# DiffMeasure.net
KiCad netlist of a schematic drawn in Altium Designer
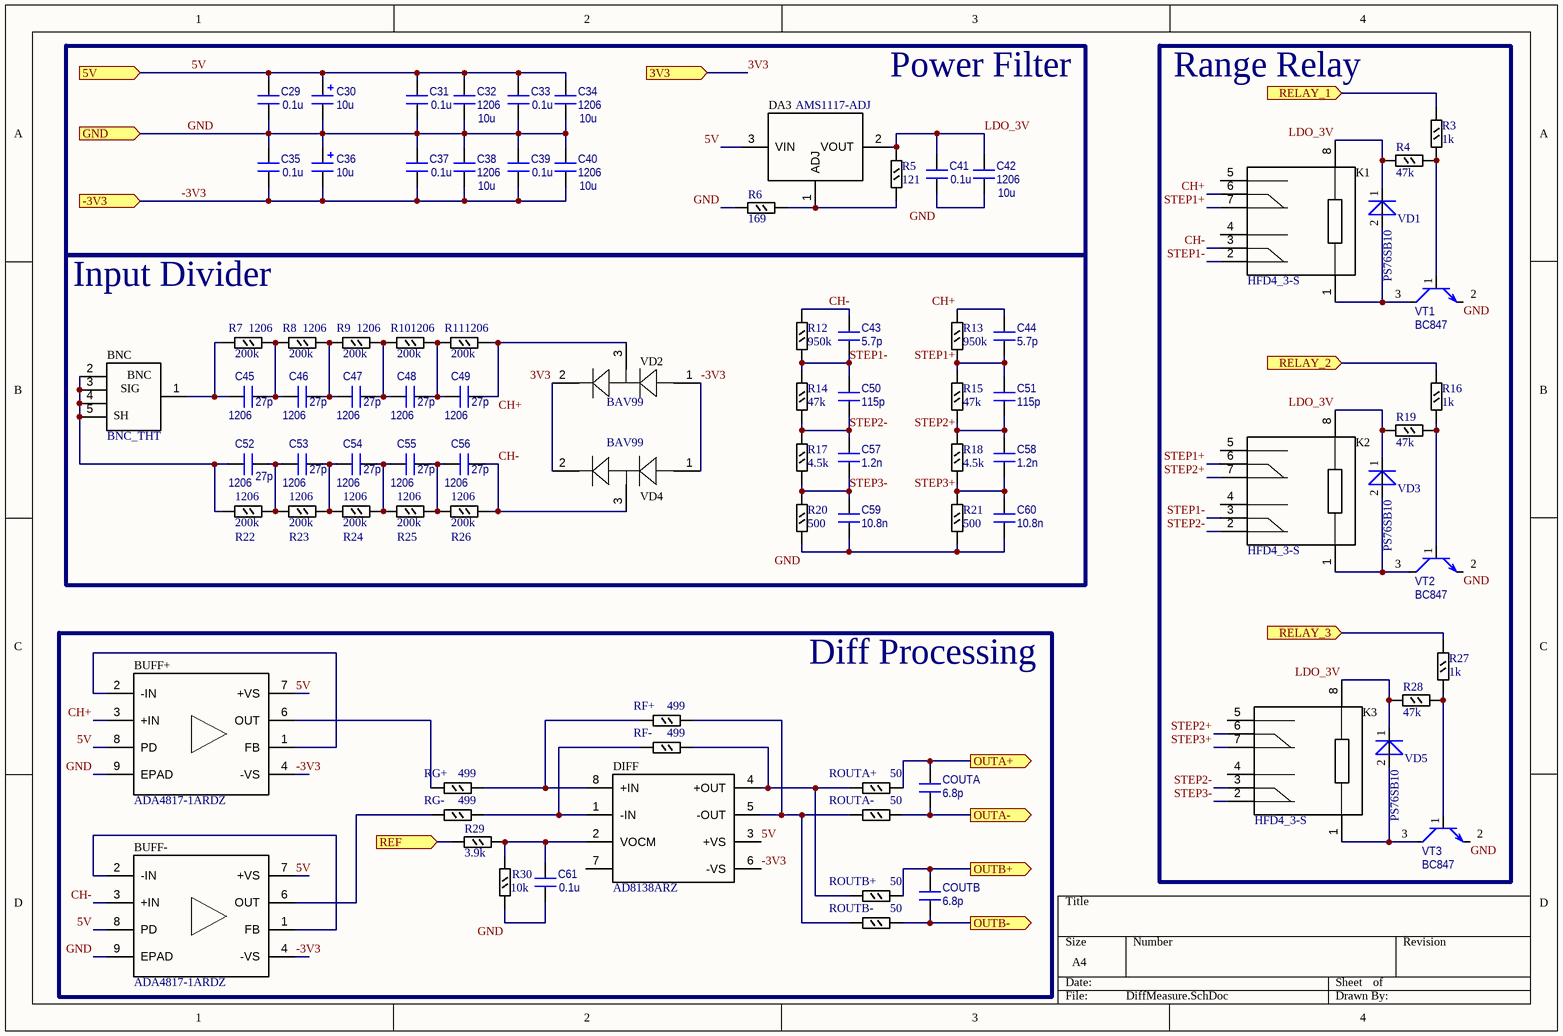
[diagram p0: DiffMeasure.SchDoc]

(export (version "E")
  (design (tool "Eeschema 10.0.6"))
  (components
    (comp (ref "BNC")
      (value "BNC_THT")
      (footprint "BNC_VERTICAL_THT_5PIN")
      (description "Generic vertical BNC jack, five through-hole terminals")
      (libsource (lib "Oscill") (part "BNC_VERTICAL_THT"))
    )
    (comp (ref "BUFF+")
      (value "ADA4817-1ARDZ")
      (footprint "ADA4817-1ARDZ_SOIC8_EP")
      (description "ADI ADA4817-1ARDZ FastFET op amp, RD-8-4 SOIC-8 with EP")
      (libsource (lib "Oscill") (part "ADA4817-1ARDZ"))
    )
    (comp (ref "BUFF-")
      (value "ADA4817-1ARDZ")
      (footprint "ADA4817-1ARDZ_SOIC8_EP")
      (description "ADI ADA4817-1ARDZ FastFET op amp, RD-8-4 SOIC-8 with EP")
      (libsource (lib "Oscill") (part "ADA4817-1ARDZ"))
    )
    (comp (ref "C29")
      (value "0.1u")
      (footprint "CAPC2012(0805)N")
      (fields (field (name "PART NUMBER") "CAPC2012(0805)"))
      (libsource (lib "SssAccesDatbase") (part "Capacitor generic"))
    )
    (comp (ref "C30")
      (value "10u")
      (footprint "CAPMP7343X310N")
      (fields (field (name "PART NUMBER") "CapTantD"))
      (libsource (lib "SssAccesDatbase") (part "Capacitor generic polar"))
    )
    (comp (ref "C31")
      (value "0.1u")
      (footprint "CAPC2012(0805)N")
      (fields (field (name "PART NUMBER") "CAPC2012(0805)"))
      (libsource (lib "SssAccesDatbase") (part "Capacitor generic"))
    )
    (comp (ref "C32")
      (value "10u")
      (footprint "CAP_CER_1206")
      (description "Cap Cer MLCC SMD 50V 2700p C0G NP0 1206 2%")
      (fields
        (field (name "PACKAGE") "1206")
        (field (name "PART NUMBER") "12065A272GAT2A")
        (field (name "MOUSER PART NUMBER") "581-12065A272G")
      )
      (libsource (lib "SssAccesDatbase") (part "Capacitor generic"))
    )
    (comp (ref "C33")
      (value "0.1u")
      (footprint "CAPC2012(0805)N")
      (fields (field (name "PART NUMBER") "CAPC2012(0805)"))
      (libsource (lib "SssAccesDatbase") (part "Capacitor generic"))
    )
    (comp (ref "C34")
      (value "10u")
      (footprint "CAP_CER_1206")
      (description "Cap Cer MLCC SMD 50V 2700p C0G NP0 1206 2%")
      (fields
        (field (name "PACKAGE") "1206")
        (field (name "PART NUMBER") "12065A272GAT2A")
        (field (name "MOUSER PART NUMBER") "581-12065A272G")
      )
      (libsource (lib "SssAccesDatbase") (part "Capacitor generic"))
    )
    (comp (ref "C35")
      (value "0.1u")
      (footprint "CAPC2012(0805)N")
      (fields (field (name "PART NUMBER") "CAPC2012(0805)"))
      (libsource (lib "SssAccesDatbase") (part "Capacitor generic"))
    )
    (comp (ref "C36")
      (value "10u")
      (footprint "CAPMP7343X310N")
      (fields (field (name "PART NUMBER") "CapTantD"))
      (libsource (lib "SssAccesDatbase") (part "Capacitor generic polar"))
    )
    (comp (ref "C37")
      (value "0.1u")
      (footprint "CAPC2012(0805)N")
      (fields (field (name "PART NUMBER") "CAPC2012(0805)"))
      (libsource (lib "SssAccesDatbase") (part "Capacitor generic"))
    )
    (comp (ref "C38")
      (value "10u")
      (footprint "CAP_CER_1206")
      (description "Cap Cer MLCC SMD 50V 2700p C0G NP0 1206 2%")
      (fields
        (field (name "PACKAGE") "1206")
        (field (name "PART NUMBER") "12065A272GAT2A")
        (field (name "MOUSER PART NUMBER") "581-12065A272G")
      )
      (libsource (lib "SssAccesDatbase") (part "Capacitor generic"))
    )
    (comp (ref "C39")
      (value "0.1u")
      (footprint "CAPC2012(0805)N")
      (fields (field (name "PART NUMBER") "CAPC2012(0805)"))
      (libsource (lib "SssAccesDatbase") (part "Capacitor generic"))
    )
    (comp (ref "C40")
      (value "10u")
      (footprint "CAP_CER_1206")
      (description "Cap Cer MLCC SMD 50V 2700p C0G NP0 1206 2%")
      (fields
        (field (name "PACKAGE") "1206")
        (field (name "PART NUMBER") "12065A272GAT2A")
        (field (name "MOUSER PART NUMBER") "581-12065A272G")
      )
      (libsource (lib "SssAccesDatbase") (part "Capacitor generic"))
    )
    (comp (ref "C41")
      (value "0.1u")
      (footprint "CAPC2012(0805)N")
      (fields (field (name "PART NUMBER") "CAPC2012(0805)"))
      (libsource (lib "SssAccesDatbase") (part "Capacitor generic"))
    )
    (comp (ref "C42")
      (value "10u")
      (footprint "CAP_CER_1206")
      (description "Cap Cer MLCC SMD 50V 2700p C0G NP0 1206 2%")
      (fields
        (field (name "PACKAGE") "1206")
        (field (name "PART NUMBER") "12065A272GAT2A")
        (field (name "MOUSER PART NUMBER") "581-12065A272G")
      )
      (libsource (lib "SssAccesDatbase") (part "Capacitor generic"))
    )
    (comp (ref "C43")
      (value "5.7p")
      (footprint "CAPC2012(0805)N")
      (fields (field (name "PART NUMBER") "CAPC2012(0805)"))
      (libsource (lib "SssAccesDatbase") (part "Capacitor generic"))
    )
    (comp (ref "C44")
      (value "5.7p")
      (footprint "CAPC2012(0805)N")
      (fields (field (name "PART NUMBER") "CAPC2012(0805)"))
      (libsource (lib "SssAccesDatbase") (part "Capacitor generic"))
    )
    (comp (ref "C45")
      (value "27p")
      (footprint "CAP_CER_1206")
      (description "Cap Cer MLCC SMD 50V 2700p C0G NP0 1206 2%")
      (fields
        (field (name "PACKAGE") "1206")
        (field (name "PART NUMBER") "12065A272GAT2A")
        (field (name "MOUSER PART NUMBER") "581-12065A272G")
      )
      (libsource (lib "SssAccesDatbase") (part "Capacitor generic"))
    )
    (comp (ref "C46")
      (value "27p")
      (footprint "CAP_CER_1206")
      (description "Cap Cer MLCC SMD 50V 2700p C0G NP0 1206 2%")
      (fields
        (field (name "PACKAGE") "1206")
        (field (name "PART NUMBER") "12065A272GAT2A")
        (field (name "MOUSER PART NUMBER") "581-12065A272G")
      )
      (libsource (lib "SssAccesDatbase") (part "Capacitor generic"))
    )
    (comp (ref "C47")
      (value "27p")
      (footprint "CAP_CER_1206")
      (description "Cap Cer MLCC SMD 50V 2700p C0G NP0 1206 2%")
      (fields
        (field (name "PACKAGE") "1206")
        (field (name "PART NUMBER") "12065A272GAT2A")
        (field (name "MOUSER PART NUMBER") "581-12065A272G")
      )
      (libsource (lib "SssAccesDatbase") (part "Capacitor generic"))
    )
    (comp (ref "C48")
      (value "27p")
      (footprint "CAP_CER_1206")
      (description "Cap Cer MLCC SMD 50V 2700p C0G NP0 1206 2%")
      (fields
        (field (name "PACKAGE") "1206")
        (field (name "PART NUMBER") "12065A272GAT2A")
        (field (name "MOUSER PART NUMBER") "581-12065A272G")
      )
      (libsource (lib "SssAccesDatbase") (part "Capacitor generic"))
    )
    (comp (ref "C49")
      (value "27p")
      (footprint "CAP_CER_1206")
      (description "Cap Cer MLCC SMD 50V 2700p C0G NP0 1206 2%")
      (fields
        (field (name "PACKAGE") "1206")
        (field (name "PART NUMBER") "12065A272GAT2A")
        (field (name "MOUSER PART NUMBER") "581-12065A272G")
      )
      (libsource (lib "SssAccesDatbase") (part "Capacitor generic"))
    )
    (comp (ref "C50")
      (value "115p")
      (footprint "CAPC2012(0805)N")
      (fields (field (name "PART NUMBER") "CAPC2012(0805)"))
      (libsource (lib "SssAccesDatbase") (part "Capacitor generic"))
    )
    (comp (ref "C51")
      (value "115p")
      (footprint "CAPC2012(0805)N")
      (fields (field (name "PART NUMBER") "CAPC2012(0805)"))
      (libsource (lib "SssAccesDatbase") (part "Capacitor generic"))
    )
    (comp (ref "C52")
      (value "27p")
      (footprint "CAP_CER_1206")
      (description "Cap Cer MLCC SMD 50V 2700p C0G NP0 1206 2%")
      (fields
        (field (name "PACKAGE") "1206")
        (field (name "PART NUMBER") "12065A272GAT2A")
        (field (name "MOUSER PART NUMBER") "581-12065A272G")
      )
      (libsource (lib "SssAccesDatbase") (part "Capacitor generic"))
    )
    (comp (ref "C53")
      (value "27p")
      (footprint "CAP_CER_1206")
      (description "Cap Cer MLCC SMD 50V 2700p C0G NP0 1206 2%")
      (fields
        (field (name "PACKAGE") "1206")
        (field (name "PART NUMBER") "12065A272GAT2A")
        (field (name "MOUSER PART NUMBER") "581-12065A272G")
      )
      (libsource (lib "SssAccesDatbase") (part "Capacitor generic"))
    )
    (comp (ref "C54")
      (value "27p")
      (footprint "CAP_CER_1206")
      (description "Cap Cer MLCC SMD 50V 2700p C0G NP0 1206 2%")
      (fields
        (field (name "PACKAGE") "1206")
        (field (name "PART NUMBER") "12065A272GAT2A")
        (field (name "MOUSER PART NUMBER") "581-12065A272G")
      )
      (libsource (lib "SssAccesDatbase") (part "Capacitor generic"))
    )
    (comp (ref "C55")
      (value "27p")
      (footprint "CAP_CER_1206")
      (description "Cap Cer MLCC SMD 50V 2700p C0G NP0 1206 2%")
      (fields
        (field (name "PACKAGE") "1206")
        (field (name "PART NUMBER") "12065A272GAT2A")
        (field (name "MOUSER PART NUMBER") "581-12065A272G")
      )
      (libsource (lib "SssAccesDatbase") (part "Capacitor generic"))
    )
    (comp (ref "C56")
      (value "27p")
      (footprint "CAP_CER_1206")
      (description "Cap Cer MLCC SMD 50V 2700p C0G NP0 1206 2%")
      (fields
        (field (name "PACKAGE") "1206")
        (field (name "PART NUMBER") "12065A272GAT2A")
        (field (name "MOUSER PART NUMBER") "581-12065A272G")
      )
      (libsource (lib "SssAccesDatbase") (part "Capacitor generic"))
    )
    (comp (ref "C57")
      (value "1.2n")
      (footprint "CAPC2012(0805)N")
      (fields (field (name "PART NUMBER") "CAPC2012(0805)"))
      (libsource (lib "SssAccesDatbase") (part "Capacitor generic"))
    )
    (comp (ref "C58")
      (value "1.2n")
      (footprint "CAPC2012(0805)N")
      (fields (field (name "PART NUMBER") "CAPC2012(0805)"))
      (libsource (lib "SssAccesDatbase") (part "Capacitor generic"))
    )
    (comp (ref "C59")
      (value "10.8n")
      (footprint "CAPC2012(0805)N")
      (fields (field (name "PART NUMBER") "CAPC2012(0805)"))
      (libsource (lib "SssAccesDatbase") (part "Capacitor generic"))
    )
    (comp (ref "C60")
      (value "10.8n")
      (footprint "CAPC2012(0805)N")
      (fields (field (name "PART NUMBER") "CAPC2012(0805)"))
      (libsource (lib "SssAccesDatbase") (part "Capacitor generic"))
    )
    (comp (ref "C61")
      (value "0.1u")
      (footprint "CAPC2012(0805)N")
      (fields (field (name "PART NUMBER") "CAPC2012(0805)"))
      (libsource (lib "SssAccesDatbase") (part "Capacitor generic"))
    )
    (comp (ref "COUTA")
      (value "6.8p")
      (footprint "CAPC2012(0805)N")
      (fields (field (name "PART NUMBER") "CAPC2012(0805)"))
      (libsource (lib "SssAccesDatbase") (part "Capacitor generic"))
    )
    (comp (ref "COUTB")
      (value "6.8p")
      (footprint "CAPC2012(0805)N")
      (fields (field (name "PART NUMBER") "CAPC2012(0805)"))
      (libsource (lib "SssAccesDatbase") (part "Capacitor generic"))
    )
    (comp (ref "DA3")
      (value "AMS1117-ADJ")
      (footprint "Oscill:AMS1117-ADJ_SOT223")
      (description "AMS1117 adjustable voltage regulator, SOT-223; tab = VOUT")
      (libsource (lib "Oscill") (part "AMS1117-ADJ"))
    )
    (comp (ref "DIFF")
      (value "AD8138ARZ")
      (footprint "AD8138ARZ_SOIC8")
      (description "ADI AD8138ARZ low distortion differential ADC driver, SOIC-8 R-8")
      (libsource (lib "Oscill") (part "AD8138ARZ"))
    )
    (comp (ref "K1")
      (value "HFD4_3-S")
      (footprint "Oscill:HFD4_3_S_SMT")
      (description "Hongfa HFD4/3-S monostable DPDT relay, standard SMT terminal")
      (libsource (lib "Oscill") (part "HFD4_3-S"))
    )
    (comp (ref "K2")
      (value "HFD4_3-S")
      (footprint "Oscill:HFD4_3_S_SMT")
      (description "Hongfa HFD4/3-S monostable DPDT relay, standard SMT terminal")
      (libsource (lib "Oscill") (part "HFD4_3-S"))
    )
    (comp (ref "K3")
      (value "HFD4_3-S")
      (footprint "Oscill:HFD4_3_S_SMT")
      (description "Hongfa HFD4/3-S monostable DPDT relay, standard SMT terminal")
      (libsource (lib "Oscill") (part "HFD4_3-S"))
    )
    (comp (ref "R3")
      (value "1k")
      (footprint "RESC2012(0805)N")
      (fields (field (name "PART NUMBER") "RESC2012(0805)"))
      (libsource (lib "") (part "Resistor 0,125W_1"))
    )
    (comp (ref "R4")
      (value "47k")
      (footprint "RESC2012(0805)N")
      (fields (field (name "PART NUMBER") "RESC2012(0805)"))
      (libsource (lib "") (part "Resistor 0,125W_3"))
    )
    (comp (ref "R5")
      (value "121")
      (footprint "RESC2012(0805)N")
      (fields (field (name "PART NUMBER") "RESC2012(0805)"))
      (libsource (lib "") (part "Resistor 0,125W_1"))
    )
    (comp (ref "R6")
      (value "169")
      (footprint "RESC2012(0805)N")
      (fields (field (name "PART NUMBER") "RESC2012(0805)"))
      (libsource (lib "SssAccesDatbase") (part "Resistor 0,125W"))
    )
    (comp (ref "R7")
      (value "200k")
      (footprint "Oscill:R_1206")
      (fields (field (name "PART NUMBER") "RESC2012(0805)") (field (name "PACKAGE") "1206"))
      (libsource (lib "SssAccesDatbase") (part "Resistor 0,125W"))
    )
    (comp (ref "R8")
      (value "200k")
      (footprint "Oscill:R_1206")
      (fields (field (name "PART NUMBER") "RESC2012(0805)") (field (name "PACKAGE") "1206"))
      (libsource (lib "SssAccesDatbase") (part "Resistor 0,125W"))
    )
    (comp (ref "R9")
      (value "200k")
      (footprint "Oscill:R_1206")
      (fields (field (name "PART NUMBER") "RESC2012(0805)") (field (name "PACKAGE") "1206"))
      (libsource (lib "SssAccesDatbase") (part "Resistor 0,125W"))
    )
    (comp (ref "R10")
      (value "200k")
      (footprint "Oscill:R_1206")
      (fields (field (name "PART NUMBER") "RESC2012(0805)") (field (name "PACKAGE") "1206"))
      (libsource (lib "SssAccesDatbase") (part "Resistor 0,125W"))
    )
    (comp (ref "R11")
      (value "200k")
      (footprint "Oscill:R_1206")
      (fields (field (name "PART NUMBER") "RESC2012(0805)") (field (name "PACKAGE") "1206"))
      (libsource (lib "SssAccesDatbase") (part "Resistor 0,125W"))
    )
    (comp (ref "R12")
      (value "950k")
      (footprint "RESC2012(0805)N")
      (fields (field (name "PART NUMBER") "RESC2012(0805)"))
      (libsource (lib "") (part "Resistor 0,125W_2"))
    )
    (comp (ref "R13")
      (value "950k")
      (footprint "RESC2012(0805)N")
      (fields (field (name "PART NUMBER") "RESC2012(0805)"))
      (libsource (lib "") (part "Resistor 0,125W_2"))
    )
    (comp (ref "R14")
      (value "47k")
      (footprint "RESC2012(0805)N")
      (fields (field (name "PART NUMBER") "RESC2012(0805)"))
      (libsource (lib "") (part "Resistor 0,125W_2"))
    )
    (comp (ref "R15")
      (value "47k")
      (footprint "RESC2012(0805)N")
      (fields (field (name "PART NUMBER") "RESC2012(0805)"))
      (libsource (lib "") (part "Resistor 0,125W_2"))
    )
    (comp (ref "R16")
      (value "1k")
      (footprint "RESC2012(0805)N")
      (fields (field (name "PART NUMBER") "RESC2012(0805)"))
      (libsource (lib "") (part "Resistor 0,125W_1"))
    )
    (comp (ref "R17")
      (value "4.5k")
      (footprint "RESC2012(0805)N")
      (fields (field (name "PART NUMBER") "RESC2012(0805)"))
      (libsource (lib "") (part "Resistor 0,125W_2"))
    )
    (comp (ref "R18")
      (value "4.5k")
      (footprint "RESC2012(0805)N")
      (fields (field (name "PART NUMBER") "RESC2012(0805)"))
      (libsource (lib "") (part "Resistor 0,125W_2"))
    )
    (comp (ref "R19")
      (value "47k")
      (footprint "RESC2012(0805)N")
      (fields (field (name "PART NUMBER") "RESC2012(0805)"))
      (libsource (lib "") (part "Resistor 0,125W_3"))
    )
    (comp (ref "R20")
      (value "500")
      (footprint "RESC2012(0805)N")
      (fields (field (name "PART NUMBER") "RESC2012(0805)"))
      (libsource (lib "") (part "Resistor 0,125W_2"))
    )
    (comp (ref "R21")
      (value "500")
      (footprint "RESC2012(0805)N")
      (fields (field (name "PART NUMBER") "RESC2012(0805)"))
      (libsource (lib "") (part "Resistor 0,125W_2"))
    )
    (comp (ref "R22")
      (value "200k")
      (footprint "Oscill:R_1206")
      (fields (field (name "PART NUMBER") "RESC2012(0805)") (field (name "PACKAGE") "1206"))
      (libsource (lib "SssAccesDatbase") (part "Resistor 0,125W"))
    )
    (comp (ref "R23")
      (value "200k")
      (footprint "Oscill:R_1206")
      (fields (field (name "PART NUMBER") "RESC2012(0805)") (field (name "PACKAGE") "1206"))
      (libsource (lib "SssAccesDatbase") (part "Resistor 0,125W"))
    )
    (comp (ref "R24")
      (value "200k")
      (footprint "Oscill:R_1206")
      (fields (field (name "PART NUMBER") "RESC2012(0805)") (field (name "PACKAGE") "1206"))
      (libsource (lib "SssAccesDatbase") (part "Resistor 0,125W"))
    )
    (comp (ref "R25")
      (value "200k")
      (footprint "Oscill:R_1206")
      (fields (field (name "PART NUMBER") "RESC2012(0805)") (field (name "PACKAGE") "1206"))
      (libsource (lib "SssAccesDatbase") (part "Resistor 0,125W"))
    )
    (comp (ref "R26")
      (value "200k")
      (footprint "Oscill:R_1206")
      (fields (field (name "PART NUMBER") "RESC2012(0805)") (field (name "PACKAGE") "1206"))
      (libsource (lib "SssAccesDatbase") (part "Resistor 0,125W"))
    )
    (comp (ref "R27")
      (value "1k")
      (footprint "RESC2012(0805)N")
      (fields (field (name "PART NUMBER") "RESC2012(0805)"))
      (libsource (lib "") (part "Resistor 0,125W_1"))
    )
    (comp (ref "R28")
      (value "47k")
      (footprint "RESC2012(0805)N")
      (fields (field (name "PART NUMBER") "RESC2012(0805)"))
      (libsource (lib "") (part "Resistor 0,125W_3"))
    )
    (comp (ref "R29")
      (value "3.9k")
      (footprint "RESC2012(0805)N")
      (fields (field (name "PART NUMBER") "RESC2012(0805)"))
      (libsource (lib "SssAccesDatbase") (part "Resistor 0,125W"))
    )
    (comp (ref "R30")
      (value "10k")
      (footprint "RESC2012(0805)N")
      (fields (field (name "PART NUMBER") "RESC2012(0805)"))
      (libsource (lib "") (part "Resistor 0,125W_1"))
    )
    (comp (ref "RF+")
      (value "499")
      (footprint "RESC2012(0805)N")
      (fields (field (name "PART NUMBER") "RESC2012(0805)"))
      (libsource (lib "SssAccesDatbase") (part "Resistor 0,125W"))
    )
    (comp (ref "RF-")
      (value "499")
      (footprint "RESC2012(0805)N")
      (fields (field (name "PART NUMBER") "RESC2012(0805)"))
      (libsource (lib "SssAccesDatbase") (part "Resistor 0,125W"))
    )
    (comp (ref "RG+")
      (value "499")
      (footprint "RESC2012(0805)N")
      (fields (field (name "PART NUMBER") "RESC2012(0805)"))
      (libsource (lib "SssAccesDatbase") (part "Resistor 0,125W"))
    )
    (comp (ref "RG-")
      (value "499")
      (footprint "RESC2012(0805)N")
      (fields (field (name "PART NUMBER") "RESC2012(0805)"))
      (libsource (lib "SssAccesDatbase") (part "Resistor 0,125W"))
    )
    (comp (ref "ROUTA+")
      (value "50")
      (footprint "RESC2012(0805)N")
      (fields (field (name "PART NUMBER") "RESC2012(0805)"))
      (libsource (lib "SssAccesDatbase") (part "Resistor 0,125W"))
    )
    (comp (ref "ROUTA-")
      (value "50")
      (footprint "RESC2012(0805)N")
      (fields (field (name "PART NUMBER") "RESC2012(0805)"))
      (libsource (lib "SssAccesDatbase") (part "Resistor 0,125W"))
    )
    (comp (ref "ROUTB+")
      (value "50")
      (footprint "RESC2012(0805)N")
      (fields (field (name "PART NUMBER") "RESC2012(0805)"))
      (libsource (lib "SssAccesDatbase") (part "Resistor 0,125W"))
    )
    (comp (ref "ROUTB-")
      (value "50")
      (footprint "RESC2012(0805)N")
      (fields (field (name "PART NUMBER") "RESC2012(0805)"))
      (libsource (lib "SssAccesDatbase") (part "Resistor 0,125W"))
    )
    (comp (ref "VD1")
      (value "PS76SB10")
      (footprint "SOD323")
      (description "Schottky Diode 30V 0,2A  SOD-323-2")
      (fields
        (field (name "PART NUMBER") "BAT54J")
        (field (name "MANUFACTURER PART NUMBER") "BAT54J,115")
        (field (name "PUBLISHER") "Altium Limited")
      )
      (libsource (lib "SssAccesDatbase") (part "Diode_C-A"))
    )
    (comp (ref "VD2")
      (value "BAV99")
      (footprint "BAV99_SOT23")
      (description "Nexperia BAV99 dual series diode, SOT23")
      (libsource (lib "Oscill") (part "BAV99"))
    )
    (comp (ref "VD3")
      (value "PS76SB10")
      (footprint "SOD323")
      (description "Schottky Diode 30V 0,2A  SOD-323-2")
      (fields
        (field (name "PART NUMBER") "BAT54J")
        (field (name "MANUFACTURER PART NUMBER") "BAT54J,115")
        (field (name "PUBLISHER") "Altium Limited")
      )
      (libsource (lib "SssAccesDatbase") (part "Diode_C-A"))
    )
    (comp (ref "VD4")
      (value "BAV99")
      (footprint "BAV99_SOT23")
      (description "Nexperia BAV99 dual series diode, SOT23")
      (libsource (lib "Oscill") (part "BAV99"))
    )
    (comp (ref "VD5")
      (value "PS76SB10")
      (footprint "SOD323")
      (description "Schottky Diode 30V 0,2A  SOD-323-2")
      (fields
        (field (name "PART NUMBER") "BAT54J")
        (field (name "MANUFACTURER PART NUMBER") "BAT54J,115")
        (field (name "PUBLISHER") "Altium Limited")
      )
      (libsource (lib "SssAccesDatbase") (part "Diode_C-A"))
    )
    (comp (ref "VT1")
      (value "BC847")
      (footprint "SOT23-3N")
      (fields (field (name "PART NUMBER") "BC848"))
      (libsource (lib "SssAccesDatbase") (part "TRANS-NPN-BEC"))
    )
    (comp (ref "VT2")
      (value "BC847")
      (footprint "SOT23-3N")
      (fields (field (name "PART NUMBER") "BC848"))
      (libsource (lib "SssAccesDatbase") (part "TRANS-NPN-BEC"))
    )
    (comp (ref "VT3")
      (value "BC847")
      (footprint "SOT23-3N")
      (fields (field (name "PART NUMBER") "BC848"))
      (libsource (lib "SssAccesDatbase") (part "TRANS-NPN-BEC"))
    )
  )
  (nets
    (net (code "1") (name "/-3V3") (class "Default")
      (node (ref "BUFF+") (pin "4") (pinfunction "-VS_4") (pintype "passive"))
      (node (ref "BUFF-") (pin "4") (pinfunction "-VS_4") (pintype "passive"))
      (node (ref "C35") (pin "2") (pinfunction "2_2") (pintype "passive"))
      (node (ref "C36") (pin "2") (pinfunction "2_2") (pintype "passive"))
      (node (ref "C37") (pin "2") (pinfunction "2_2") (pintype "passive"))
      (node (ref "C38") (pin "2") (pinfunction "2_2") (pintype "passive"))
      (node (ref "C39") (pin "2") (pinfunction "2_2") (pintype "passive"))
      (node (ref "C40") (pin "2") (pinfunction "2_2") (pintype "passive"))
      (node (ref "DIFF") (pin "6") (pinfunction "-VS_6") (pintype "passive"))
      (node (ref "VD2") (pin "1") (pinfunction "A1_1") (pintype "passive"))
      (node (ref "VD4") (pin "1") (pinfunction "A1_1") (pintype "passive"))
    )
    (net (code "2") (name "/3V3") (class "Default")
      (node (ref "VD2") (pin "2") (pinfunction "K2_2") (pintype "passive"))
      (node (ref "VD4") (pin "2") (pinfunction "K2_2") (pintype "passive"))
    )
    (net (code "3") (name "/5V") (class "Default")
      (node (ref "BUFF+") (pin "7") (pinfunction "+VS_7") (pintype "passive"))
      (node (ref "BUFF+") (pin "8") (pinfunction "PD_8") (pintype "passive"))
      (node (ref "BUFF-") (pin "7") (pinfunction "+VS_7") (pintype "passive"))
      (node (ref "BUFF-") (pin "8") (pinfunction "PD_8") (pintype "passive"))
      (node (ref "C29") (pin "1") (pinfunction "1_1") (pintype "passive"))
      (node (ref "C30") (pin "1") (pinfunction "1_1") (pintype "passive"))
      (node (ref "C31") (pin "1") (pinfunction "1_1") (pintype "passive"))
      (node (ref "C32") (pin "1") (pinfunction "1_1") (pintype "passive"))
      (node (ref "C33") (pin "1") (pinfunction "1_1") (pintype "passive"))
      (node (ref "C34") (pin "1") (pinfunction "1_1") (pintype "passive"))
      (node (ref "DA3") (pin "3") (pinfunction "VIN_3") (pintype "passive"))
      (node (ref "DIFF") (pin "3") (pinfunction "+VS_3") (pintype "passive"))
    )
    (net (code "4") (name "/CH+") (class "Default")
      (node (ref "BUFF+") (pin "3") (pinfunction "+IN_3") (pintype "passive"))
      (node (ref "C44") (pin "1") (pinfunction "1_1") (pintype "passive"))
      (node (ref "C49") (pin "2") (pinfunction "2_2") (pintype "passive"))
      (node (ref "K1") (pin "6") (pintype "passive"))
      (node (ref "R11") (pin "2") (pinfunction "2_2") (pintype "passive"))
      (node (ref "R13") (pin "2") (pinfunction "2_2") (pintype "passive"))
      (node (ref "VD2") (pin "3") (pinfunction "K1_A2_3") (pintype "passive"))
    )
    (net (code "5") (name "/CH-") (class "Default")
      (node (ref "BUFF-") (pin "3") (pinfunction "+IN_3") (pintype "passive"))
      (node (ref "C43") (pin "1") (pinfunction "1_1") (pintype "passive"))
      (node (ref "C56") (pin "2") (pinfunction "2_2") (pintype "passive"))
      (node (ref "K1") (pin "3") (pintype "passive"))
      (node (ref "R12") (pin "2") (pinfunction "2_2") (pintype "passive"))
      (node (ref "R26") (pin "2") (pinfunction "2_2") (pintype "passive"))
      (node (ref "VD4") (pin "3") (pinfunction "K1_A2_3") (pintype "passive"))
    )
    (net (code "6") (name "/GND") (class "Default")
      (node (ref "BUFF+") (pin "9") (pinfunction "EPAD_9") (pintype "passive"))
      (node (ref "BUFF-") (pin "9") (pinfunction "EPAD_9") (pintype "passive"))
      (node (ref "C29") (pin "2") (pinfunction "2_2") (pintype "passive"))
      (node (ref "C30") (pin "2") (pinfunction "2_2") (pintype "passive"))
      (node (ref "C31") (pin "2") (pinfunction "2_2") (pintype "passive"))
      (node (ref "C32") (pin "2") (pinfunction "2_2") (pintype "passive"))
      (node (ref "C33") (pin "2") (pinfunction "2_2") (pintype "passive"))
      (node (ref "C34") (pin "2") (pinfunction "2_2") (pintype "passive"))
      (node (ref "C35") (pin "1") (pinfunction "1_1") (pintype "passive"))
      (node (ref "C36") (pin "1") (pinfunction "1_1") (pintype "passive"))
      (node (ref "C37") (pin "1") (pinfunction "1_1") (pintype "passive"))
      (node (ref "C38") (pin "1") (pinfunction "1_1") (pintype "passive"))
      (node (ref "C39") (pin "1") (pinfunction "1_1") (pintype "passive"))
      (node (ref "C40") (pin "1") (pinfunction "1_1") (pintype "passive"))
      (node (ref "C41") (pin "2") (pinfunction "2_2") (pintype "passive"))
      (node (ref "C42") (pin "2") (pinfunction "2_2") (pintype "passive"))
      (node (ref "C59") (pin "2") (pinfunction "2_2") (pintype "passive"))
      (node (ref "C60") (pin "2") (pinfunction "2_2") (pintype "passive"))
      (node (ref "C61") (pin "2") (pinfunction "2_2") (pintype "passive"))
      (node (ref "R20") (pin "1") (pinfunction "1_1") (pintype "passive"))
      (node (ref "R21") (pin "1") (pinfunction "1_1") (pintype "passive"))
      (node (ref "R30") (pin "2") (pinfunction "2_2") (pintype "passive"))
      (node (ref "R6") (pin "1") (pinfunction "1_1") (pintype "passive"))
      (node (ref "VT1") (pin "2") (pinfunction "E_2") (pintype "passive"))
      (node (ref "VT2") (pin "2") (pinfunction "E_2") (pintype "passive"))
      (node (ref "VT3") (pin "2") (pinfunction "E_2") (pintype "passive"))
    )
    (net (code "7") (name "/LDO_3V") (class "Default")
      (node (ref "C41") (pin "1") (pinfunction "1_1") (pintype "passive"))
      (node (ref "C42") (pin "1") (pinfunction "1_1") (pintype "passive"))
      (node (ref "DA3") (pin "2") (pinfunction "VOUT_2") (pintype "passive"))
      (node (ref "K1") (pin "8") (pinfunction "COIL-_8") (pintype "passive"))
      (node (ref "K2") (pin "8") (pinfunction "COIL-_8") (pintype "passive"))
      (node (ref "K3") (pin "8") (pinfunction "COIL-_8") (pintype "passive"))
      (node (ref "R19") (pin "2") (pinfunction "2_2") (pintype "passive"))
      (node (ref "R28") (pin "2") (pinfunction "2_2") (pintype "passive"))
      (node (ref "R4") (pin "2") (pinfunction "2_2") (pintype "passive"))
      (node (ref "R5") (pin "1") (pinfunction "1_1") (pintype "passive"))
      (node (ref "VD1") (pin "1") (pinfunction "C_1") (pintype "passive"))
      (node (ref "VD3") (pin "1") (pinfunction "C_1") (pintype "passive"))
      (node (ref "VD5") (pin "1") (pinfunction "C_1") (pintype "passive"))
    )
    (net (code "8") (name "/OUTA+") (class "Default")
      (node (ref "COUTA") (pin "1") (pinfunction "1_1") (pintype "passive"))
      (node (ref "ROUTA+") (pin "2") (pinfunction "2_2") (pintype "passive"))
    )
    (net (code "9") (name "/OUTA-") (class "Default")
      (node (ref "COUTA") (pin "2") (pinfunction "2_2") (pintype "passive"))
      (node (ref "ROUTA-") (pin "2") (pinfunction "2_2") (pintype "passive"))
    )
    (net (code "10") (name "/OUTB+") (class "Default")
      (node (ref "COUTB") (pin "1") (pinfunction "1_1") (pintype "passive"))
      (node (ref "ROUTB+") (pin "2") (pinfunction "2_2") (pintype "passive"))
    )
    (net (code "11") (name "/OUTB-") (class "Default")
      (node (ref "COUTB") (pin "2") (pinfunction "2_2") (pintype "passive"))
      (node (ref "ROUTB-") (pin "2") (pinfunction "2_2") (pintype "passive"))
    )
    (net (code "12") (name "/REF") (class "Default")
      (node (ref "R29") (pin "1") (pinfunction "1_1") (pintype "passive"))
    )
    (net (code "13") (name "/RELAY_1") (class "Default")
      (node (ref "R3") (pin "1") (pinfunction "1_1") (pintype "passive"))
    )
    (net (code "14") (name "/RELAY_2") (class "Default")
      (node (ref "R16") (pin "1") (pinfunction "1_1") (pintype "passive"))
    )
    (net (code "15") (name "/RELAY_3") (class "Default")
      (node (ref "R27") (pin "1") (pinfunction "1_1") (pintype "passive"))
    )
    (net (code "16") (name "/STEP1+") (class "Default")
      (node (ref "C44") (pin "2") (pinfunction "2_2") (pintype "passive"))
      (node (ref "C51") (pin "1") (pinfunction "1_1") (pintype "passive"))
      (node (ref "K1") (pin "7") (pintype "passive"))
      (node (ref "K2") (pin "6") (pintype "passive"))
      (node (ref "R13") (pin "1") (pinfunction "1_1") (pintype "passive"))
      (node (ref "R15") (pin "2") (pinfunction "2_2") (pintype "passive"))
    )
    (net (code "17") (name "/STEP1-") (class "Default")
      (node (ref "C43") (pin "2") (pinfunction "2_2") (pintype "passive"))
      (node (ref "C50") (pin "1") (pinfunction "1_1") (pintype "passive"))
      (node (ref "K1") (pin "2") (pintype "passive"))
      (node (ref "K2") (pin "3") (pintype "passive"))
      (node (ref "R12") (pin "1") (pinfunction "1_1") (pintype "passive"))
      (node (ref "R14") (pin "2") (pinfunction "2_2") (pintype "passive"))
    )
    (net (code "18") (name "/STEP2+") (class "Default")
      (node (ref "C51") (pin "2") (pinfunction "2_2") (pintype "passive"))
      (node (ref "C58") (pin "1") (pinfunction "1_1") (pintype "passive"))
      (node (ref "K2") (pin "7") (pintype "passive"))
      (node (ref "K3") (pin "6") (pintype "passive"))
      (node (ref "R15") (pin "1") (pinfunction "1_1") (pintype "passive"))
      (node (ref "R18") (pin "2") (pinfunction "2_2") (pintype "passive"))
    )
    (net (code "19") (name "/STEP2-") (class "Default")
      (node (ref "C50") (pin "2") (pinfunction "2_2") (pintype "passive"))
      (node (ref "C57") (pin "1") (pinfunction "1_1") (pintype "passive"))
      (node (ref "K2") (pin "2") (pintype "passive"))
      (node (ref "K3") (pin "3") (pintype "passive"))
      (node (ref "R14") (pin "1") (pinfunction "1_1") (pintype "passive"))
      (node (ref "R17") (pin "2") (pinfunction "2_2") (pintype "passive"))
    )
    (net (code "20") (name "/STEP3+") (class "Default")
      (node (ref "C58") (pin "2") (pinfunction "2_2") (pintype "passive"))
      (node (ref "C60") (pin "1") (pinfunction "1_1") (pintype "passive"))
      (node (ref "K3") (pin "7") (pintype "passive"))
      (node (ref "R18") (pin "1") (pinfunction "1_1") (pintype "passive"))
      (node (ref "R21") (pin "2") (pinfunction "2_2") (pintype "passive"))
    )
    (net (code "21") (name "/STEP3-") (class "Default")
      (node (ref "C57") (pin "2") (pinfunction "2_2") (pintype "passive"))
      (node (ref "C59") (pin "1") (pinfunction "1_1") (pintype "passive"))
      (node (ref "K3") (pin "2") (pintype "passive"))
      (node (ref "R17") (pin "1") (pinfunction "1_1") (pintype "passive"))
      (node (ref "R20") (pin "2") (pinfunction "2_2") (pintype "passive"))
    )
    (net (code "22") (name "Net-(BNC-SHIELD-Pad2)") (class "Default")
      (node (ref "BNC") (pin "2") (pinfunction "SHIELD_2") (pintype "passive"))
      (node (ref "BNC") (pin "3") (pinfunction "SHIELD_3") (pintype "passive"))
      (node (ref "BNC") (pin "4") (pinfunction "SHIELD_4") (pintype "passive"))
      (node (ref "BNC") (pin "5") (pinfunction "SHIELD_5") (pintype "passive"))
      (node (ref "C52") (pin "1") (pinfunction "1_1") (pintype "passive"))
      (node (ref "R22") (pin "1") (pinfunction "1_1") (pintype "passive"))
    )
    (net (code "23") (name "Net-(BNC-SIGNAL)") (class "Default")
      (node (ref "BNC") (pin "1") (pinfunction "SIGNAL_1") (pintype "passive"))
      (node (ref "C45") (pin "1") (pinfunction "1_1") (pintype "passive"))
      (node (ref "R7") (pin "1") (pinfunction "1_1") (pintype "passive"))
    )
    (net (code "24") (name "Net-(BUFF+--IN)") (class "Default")
      (node (ref "BUFF+") (pin "1") (pinfunction "FB_1") (pintype "passive"))
      (node (ref "BUFF+") (pin "2") (pinfunction "-IN_2") (pintype "passive"))
    )
    (net (code "25") (name "Net-(BUFF+-OUT)") (class "Default")
      (node (ref "BUFF+") (pin "6") (pinfunction "OUT_6") (pintype "passive"))
      (node (ref "RG+") (pin "1") (pinfunction "1_1") (pintype "passive"))
    )
    (net (code "26") (name "Net-(BUFF---IN)") (class "Default")
      (node (ref "BUFF-") (pin "1") (pinfunction "FB_1") (pintype "passive"))
      (node (ref "BUFF-") (pin "2") (pinfunction "-IN_2") (pintype "passive"))
    )
    (net (code "27") (name "Net-(BUFF--OUT)") (class "Default")
      (node (ref "BUFF-") (pin "6") (pinfunction "OUT_6") (pintype "passive"))
      (node (ref "RG-") (pin "1") (pinfunction "1_1") (pintype "passive"))
    )
    (net (code "28") (name "Net-(C45-Pad2)") (class "Default")
      (node (ref "C45") (pin "2") (pinfunction "2_2") (pintype "passive"))
      (node (ref "C46") (pin "1") (pinfunction "1_1") (pintype "passive"))
      (node (ref "R7") (pin "2") (pinfunction "2_2") (pintype "passive"))
      (node (ref "R8") (pin "1") (pinfunction "1_1") (pintype "passive"))
    )
    (net (code "29") (name "Net-(C46-Pad2)") (class "Default")
      (node (ref "C46") (pin "2") (pinfunction "2_2") (pintype "passive"))
      (node (ref "C47") (pin "1") (pinfunction "1_1") (pintype "passive"))
      (node (ref "R8") (pin "2") (pinfunction "2_2") (pintype "passive"))
      (node (ref "R9") (pin "1") (pinfunction "1_1") (pintype "passive"))
    )
    (net (code "30") (name "Net-(C47-Pad2)") (class "Default")
      (node (ref "C47") (pin "2") (pinfunction "2_2") (pintype "passive"))
      (node (ref "C48") (pin "1") (pinfunction "1_1") (pintype "passive"))
      (node (ref "R10") (pin "1") (pinfunction "1_1") (pintype "passive"))
      (node (ref "R9") (pin "2") (pinfunction "2_2") (pintype "passive"))
    )
    (net (code "31") (name "Net-(C48-Pad2)") (class "Default")
      (node (ref "C48") (pin "2") (pinfunction "2_2") (pintype "passive"))
      (node (ref "C49") (pin "1") (pinfunction "1_1") (pintype "passive"))
      (node (ref "R10") (pin "2") (pinfunction "2_2") (pintype "passive"))
      (node (ref "R11") (pin "1") (pinfunction "1_1") (pintype "passive"))
    )
    (net (code "32") (name "Net-(C52-Pad2)") (class "Default")
      (node (ref "C52") (pin "2") (pinfunction "2_2") (pintype "passive"))
      (node (ref "C53") (pin "1") (pinfunction "1_1") (pintype "passive"))
      (node (ref "R22") (pin "2") (pinfunction "2_2") (pintype "passive"))
      (node (ref "R23") (pin "1") (pinfunction "1_1") (pintype "passive"))
    )
    (net (code "33") (name "Net-(C53-Pad2)") (class "Default")
      (node (ref "C53") (pin "2") (pinfunction "2_2") (pintype "passive"))
      (node (ref "C54") (pin "1") (pinfunction "1_1") (pintype "passive"))
      (node (ref "R23") (pin "2") (pinfunction "2_2") (pintype "passive"))
      (node (ref "R24") (pin "1") (pinfunction "1_1") (pintype "passive"))
    )
    (net (code "34") (name "Net-(C54-Pad2)") (class "Default")
      (node (ref "C54") (pin "2") (pinfunction "2_2") (pintype "passive"))
      (node (ref "C55") (pin "1") (pinfunction "1_1") (pintype "passive"))
      (node (ref "R24") (pin "2") (pinfunction "2_2") (pintype "passive"))
      (node (ref "R25") (pin "1") (pinfunction "1_1") (pintype "passive"))
    )
    (net (code "35") (name "Net-(C55-Pad2)") (class "Default")
      (node (ref "C55") (pin "2") (pinfunction "2_2") (pintype "passive"))
      (node (ref "C56") (pin "1") (pinfunction "1_1") (pintype "passive"))
      (node (ref "R25") (pin "2") (pinfunction "2_2") (pintype "passive"))
      (node (ref "R26") (pin "1") (pinfunction "1_1") (pintype "passive"))
    )
    (net (code "36") (name "Net-(DA3-ADJ)") (class "Default")
      (node (ref "DA3") (pin "1") (pinfunction "ADJ_1") (pintype "passive"))
      (node (ref "R5") (pin "2") (pinfunction "2_2") (pintype "passive"))
      (node (ref "R6") (pin "2") (pinfunction "2_2") (pintype "passive"))
    )
    (net (code "37") (name "Net-(DIFF-+IN)") (class "Default")
      (node (ref "DIFF") (pin "8") (pinfunction "+IN_8") (pintype "passive"))
      (node (ref "RF+") (pin "1") (pinfunction "1_1") (pintype "passive"))
      (node (ref "RG+") (pin "2") (pinfunction "2_2") (pintype "passive"))
    )
    (net (code "38") (name "Net-(DIFF-+OUT)") (class "Default")
      (node (ref "DIFF") (pin "4") (pinfunction "+OUT_4") (pintype "passive"))
      (node (ref "RF-") (pin "2") (pinfunction "2_2") (pintype "passive"))
      (node (ref "ROUTA+") (pin "1") (pinfunction "1_1") (pintype "passive"))
      (node (ref "ROUTB+") (pin "1") (pinfunction "1_1") (pintype "passive"))
    )
    (net (code "39") (name "Net-(DIFF--IN)") (class "Default")
      (node (ref "DIFF") (pin "1") (pinfunction "-IN_1") (pintype "passive"))
      (node (ref "RF-") (pin "1") (pinfunction "1_1") (pintype "passive"))
      (node (ref "RG-") (pin "2") (pinfunction "2_2") (pintype "passive"))
    )
    (net (code "40") (name "Net-(DIFF--OUT)") (class "Default")
      (node (ref "DIFF") (pin "5") (pinfunction "-OUT_5") (pintype "passive"))
      (node (ref "RF+") (pin "2") (pinfunction "2_2") (pintype "passive"))
      (node (ref "ROUTA-") (pin "1") (pinfunction "1_1") (pintype "passive"))
      (node (ref "ROUTB-") (pin "1") (pinfunction "1_1") (pintype "passive"))
    )
    (net (code "41") (name "Net-(DIFF-VOCM)") (class "Default")
      (node (ref "C61") (pin "1") (pinfunction "1_1") (pintype "passive"))
      (node (ref "DIFF") (pin "2") (pinfunction "VOCM_2") (pintype "passive"))
      (node (ref "R29") (pin "2") (pinfunction "2_2") (pintype "passive"))
      (node (ref "R30") (pin "1") (pinfunction "1_1") (pintype "passive"))
    )
    (net (code "42") (name "Net-(K1-COIL+)") (class "Default")
      (node (ref "K1") (pin "1") (pinfunction "COIL+_1") (pintype "passive"))
      (node (ref "VD1") (pin "2") (pinfunction "A_2") (pintype "passive"))
      (node (ref "VT1") (pin "3") (pinfunction "C_3") (pintype "passive"))
    )
    (net (code "43") (name "Net-(K2-COIL+)") (class "Default")
      (node (ref "K2") (pin "1") (pinfunction "COIL+_1") (pintype "passive"))
      (node (ref "VD3") (pin "2") (pinfunction "A_2") (pintype "passive"))
      (node (ref "VT2") (pin "3") (pinfunction "C_3") (pintype "passive"))
    )
    (net (code "44") (name "Net-(K3-COIL+)") (class "Default")
      (node (ref "K3") (pin "1") (pinfunction "COIL+_1") (pintype "passive"))
      (node (ref "VD5") (pin "2") (pinfunction "A_2") (pintype "passive"))
      (node (ref "VT3") (pin "3") (pinfunction "C_3") (pintype "passive"))
    )
    (net (code "45") (name "Net-(VT1-B)") (class "Default")
      (node (ref "R3") (pin "2") (pinfunction "2_2") (pintype "passive"))
      (node (ref "R4") (pin "1") (pinfunction "1_1") (pintype "passive"))
      (node (ref "VT1") (pin "1") (pinfunction "B_1") (pintype "passive"))
    )
    (net (code "46") (name "Net-(VT2-B)") (class "Default")
      (node (ref "R16") (pin "2") (pinfunction "2_2") (pintype "passive"))
      (node (ref "R19") (pin "1") (pinfunction "1_1") (pintype "passive"))
      (node (ref "VT2") (pin "1") (pinfunction "B_1") (pintype "passive"))
    )
    (net (code "47") (name "Net-(VT3-B)") (class "Default")
      (node (ref "R27") (pin "2") (pinfunction "2_2") (pintype "passive"))
      (node (ref "R28") (pin "1") (pinfunction "1_1") (pintype "passive"))
      (node (ref "VT3") (pin "1") (pinfunction "B_1") (pintype "passive"))
    )
    (net (code "48") (name "unconnected-(DIFF-Pad7)") (class "Default")
      (node (ref "DIFF") (pin "7") (pintype "passive"))
    )
    (net (code "49") (name "unconnected-(K1-Pad4)") (class "Default")
      (node (ref "K1") (pin "4") (pintype "passive"))
    )
    (net (code "50") (name "unconnected-(K1-Pad5)") (class "Default")
      (node (ref "K1") (pin "5") (pintype "passive"))
    )
    (net (code "51") (name "unconnected-(K2-Pad4)") (class "Default")
      (node (ref "K2") (pin "4") (pintype "passive"))
    )
    (net (code "52") (name "unconnected-(K2-Pad5)") (class "Default")
      (node (ref "K2") (pin "5") (pintype "passive"))
    )
    (net (code "53") (name "unconnected-(K3-Pad4)") (class "Default")
      (node (ref "K3") (pin "4") (pintype "passive"))
    )
    (net (code "54") (name "unconnected-(K3-Pad5)") (class "Default")
      (node (ref "K3") (pin "5") (pintype "passive"))
    )
  )
)
